# quad_vca_main.net
KiCad netlist of a schematic drawn in EAGLE
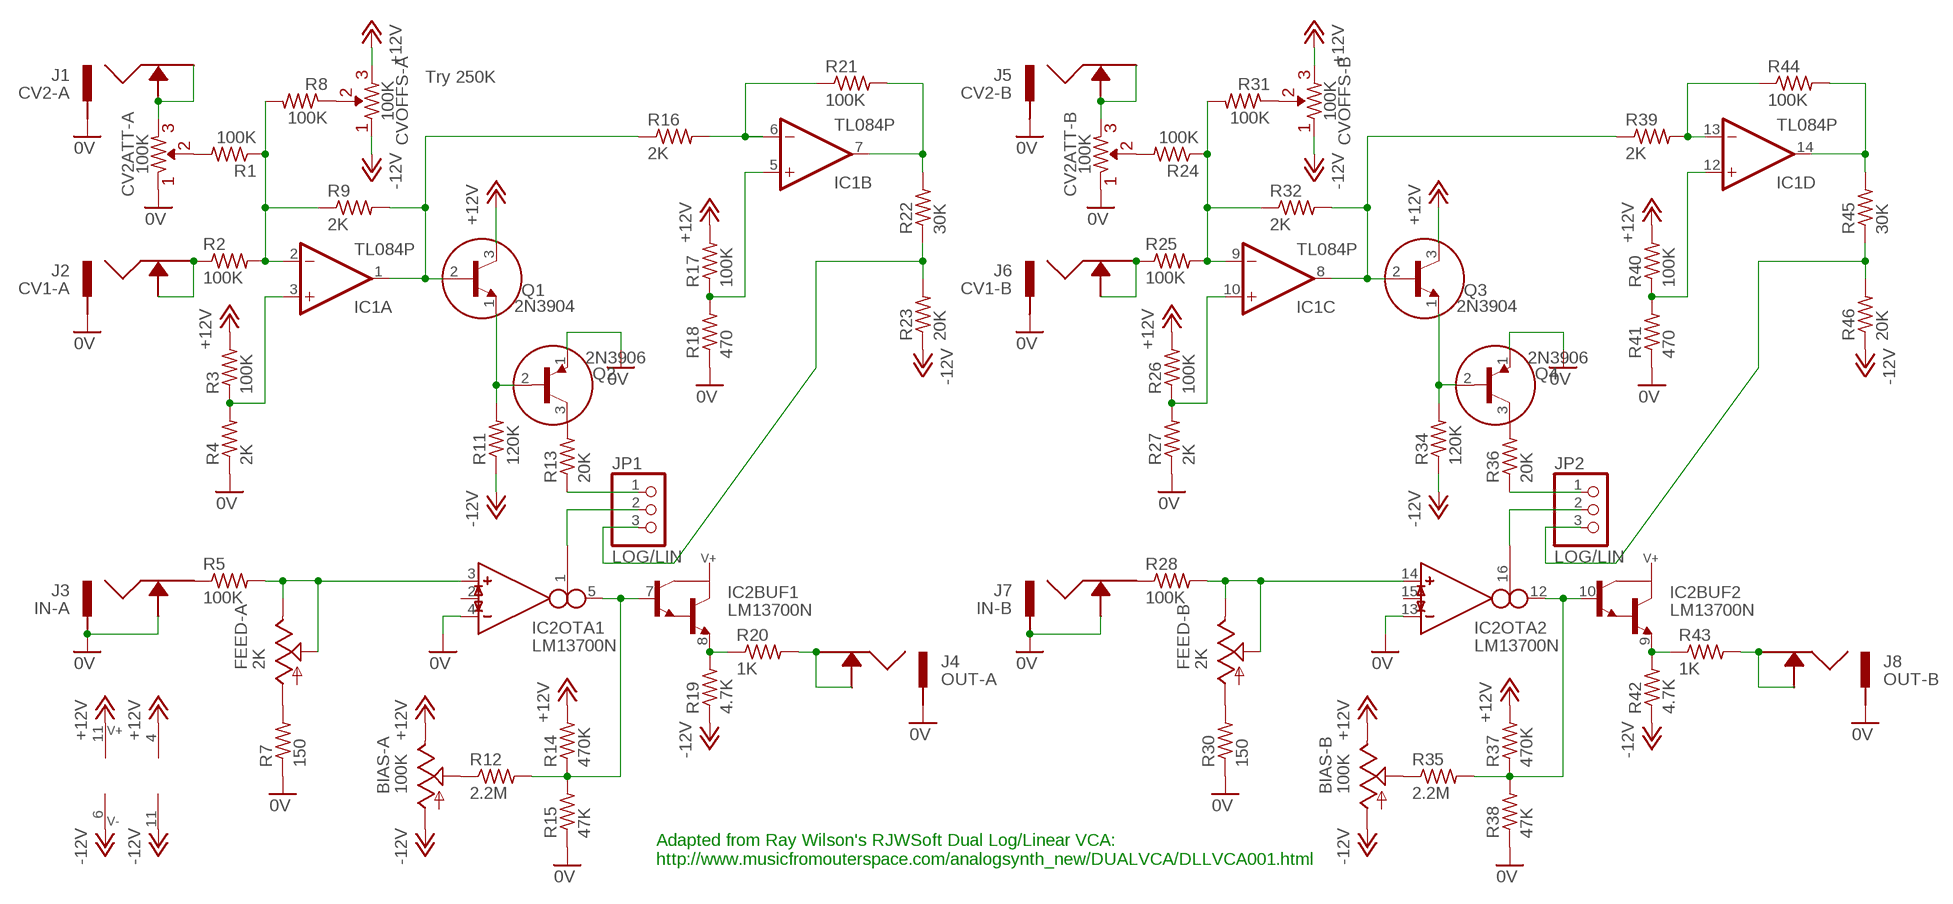
[diagram p0: schematic, sheet 1]

(export (version "E")
  (design (tool "Eeschema 10.0.6"))
  (components
    (comp (ref "BIAS-A")
      (value "100K")
      (footprint "eagle-import:PT-10S")
      (libsource (lib "eagle-import") (part "TRIM_US-PT10S"))
    )
    (comp (ref "BIAS-B")
      (value "100K")
      (footprint "eagle-import:PT-10S")
      (libsource (lib "eagle-import") (part "TRIM_US-PT10S"))
    )
    (comp (ref "CV2ATT-A")
      (value "100K")
      (footprint "eagle-import:R-VAR")
      (libsource (lib "eagle-import") (part "R-VAR"))
    )
    (comp (ref "CV2ATT-B")
      (value "100K")
      (footprint "eagle-import:R-VAR")
      (libsource (lib "eagle-import") (part "R-VAR"))
    )
    (comp (ref "CVOFFS-A")
      (value "100K")
      (footprint "eagle-import:R-VAR")
      (libsource (lib "eagle-import") (part "R-VAR"))
    )
    (comp (ref "CVOFFS-B")
      (value "100K")
      (footprint "eagle-import:R-VAR")
      (libsource (lib "eagle-import") (part "R-VAR"))
    )
    (comp (ref "FEED-A")
      (value "2K")
      (footprint "eagle-import:PT-10S")
      (libsource (lib "eagle-import") (part "TRIM_US-PT10S"))
    )
    (comp (ref "FEED-B")
      (value "2K")
      (footprint "eagle-import:PT-10S")
      (libsource (lib "eagle-import") (part "TRIM_US-PT10S"))
    )
    (comp (ref "IC1")
      (value "TL084P")
      (footprint "eagle-import:DIL14")
      (libsource (lib "eagle-import") (part "TL084P"))
    )
    (comp (ref "IC2")
      (value "LM13700N")
      (footprint "eagle-import:DIL16")
      (libsource (lib "eagle-import") (part "LM13700N"))
    )
    (comp (ref "J1")
      (value "CV2-A")
      (footprint "eagle-import:ACJM-MV35-2S")
      (libsource (lib "eagle-import") (part "ACJM-MV35-2S"))
    )
    (comp (ref "J2")
      (value "CV1-A")
      (footprint "eagle-import:ACJM-MV35-2S")
      (libsource (lib "eagle-import") (part "ACJM-MV35-2S"))
    )
    (comp (ref "J3")
      (value "IN-A")
      (footprint "eagle-import:ACJM-MV35-2S")
      (libsource (lib "eagle-import") (part "ACJM-MV35-2S"))
    )
    (comp (ref "J4")
      (value "OUT-A")
      (footprint "eagle-import:ACJM-MV35-2S")
      (libsource (lib "eagle-import") (part "ACJM-MV35-2S"))
    )
    (comp (ref "J5")
      (value "CV2-B")
      (footprint "eagle-import:ACJM-MV35-2S")
      (libsource (lib "eagle-import") (part "ACJM-MV35-2S"))
    )
    (comp (ref "J6")
      (value "CV1-B")
      (footprint "eagle-import:ACJM-MV35-2S")
      (libsource (lib "eagle-import") (part "ACJM-MV35-2S"))
    )
    (comp (ref "J7")
      (value "IN-B")
      (footprint "eagle-import:ACJM-MV35-2S")
      (libsource (lib "eagle-import") (part "ACJM-MV35-2S"))
    )
    (comp (ref "J8")
      (value "OUT-B")
      (footprint "eagle-import:ACJM-MV35-2S")
      (libsource (lib "eagle-import") (part "ACJM-MV35-2S"))
    )
    (comp (ref "JP1")
      (value "LOG/LIN")
      (footprint "eagle-import:1X03")
      (libsource (lib "eagle-import") (part "PINHD-1X3"))
    )
    (comp (ref "JP2")
      (value "LOG/LIN")
      (footprint "eagle-import:1X03")
      (libsource (lib "eagle-import") (part "PINHD-1X3"))
    )
    (comp (ref "Q1")
      (value "2N3904")
      (footprint "eagle-import:TO92")
      (libsource (lib "eagle-import") (part "2N3904"))
    )
    (comp (ref "Q2")
      (value "2N3906")
      (footprint "eagle-import:TO92")
      (libsource (lib "eagle-import") (part "2N3906"))
    )
    (comp (ref "Q3")
      (value "2N3904")
      (footprint "eagle-import:TO92")
      (libsource (lib "eagle-import") (part "2N3904"))
    )
    (comp (ref "Q4")
      (value "2N3906")
      (footprint "eagle-import:TO92")
      (libsource (lib "eagle-import") (part "2N3906"))
    )
    (comp (ref "R1")
      (value "100K")
      (footprint "eagle-import:0207_7")
      (libsource (lib "eagle-import") (part "R-US_0207/7"))
    )
    (comp (ref "R2")
      (value "100K")
      (footprint "eagle-import:0207_7")
      (libsource (lib "eagle-import") (part "R-US_0207/7"))
    )
    (comp (ref "R3")
      (value "100K")
      (footprint "eagle-import:0207_7")
      (libsource (lib "eagle-import") (part "R-US_0207/7"))
    )
    (comp (ref "R4")
      (value "2K")
      (footprint "eagle-import:0207_7")
      (libsource (lib "eagle-import") (part "R-US_0207/7"))
    )
    (comp (ref "R5")
      (value "100K")
      (footprint "eagle-import:0207_7")
      (libsource (lib "eagle-import") (part "R-US_0207/7"))
    )
    (comp (ref "R7")
      (value "150")
      (footprint "eagle-import:0207_7")
      (libsource (lib "eagle-import") (part "R-US_0207/7"))
    )
    (comp (ref "R8")
      (value "100K")
      (footprint "eagle-import:0207_7")
      (libsource (lib "eagle-import") (part "R-US_0207/7"))
    )
    (comp (ref "R9")
      (value "2K")
      (footprint "eagle-import:0207_7")
      (libsource (lib "eagle-import") (part "R-US_0207/7"))
    )
    (comp (ref "R11")
      (value "120K")
      (footprint "eagle-import:0207_7")
      (libsource (lib "eagle-import") (part "R-US_0207/7"))
    )
    (comp (ref "R12")
      (value "2.2M")
      (footprint "eagle-import:0207_7")
      (libsource (lib "eagle-import") (part "R-US_0207/7"))
    )
    (comp (ref "R13")
      (value "20K")
      (footprint "eagle-import:0207_7")
      (libsource (lib "eagle-import") (part "R-US_0207/7"))
    )
    (comp (ref "R14")
      (value "470K")
      (footprint "eagle-import:0207_7")
      (libsource (lib "eagle-import") (part "R-US_0207/7"))
    )
    (comp (ref "R15")
      (value "47K")
      (footprint "eagle-import:0207_7")
      (libsource (lib "eagle-import") (part "R-US_0207/7"))
    )
    (comp (ref "R16")
      (value "2K")
      (footprint "eagle-import:0207_7")
      (libsource (lib "eagle-import") (part "R-US_0207/7"))
    )
    (comp (ref "R17")
      (value "100K")
      (footprint "eagle-import:0207_7")
      (libsource (lib "eagle-import") (part "R-US_0207/7"))
    )
    (comp (ref "R18")
      (value "470")
      (footprint "eagle-import:0207_7")
      (libsource (lib "eagle-import") (part "R-US_0207/7"))
    )
    (comp (ref "R19")
      (value "4.7K")
      (footprint "eagle-import:0207_7")
      (libsource (lib "eagle-import") (part "R-US_0207/7"))
    )
    (comp (ref "R20")
      (value "1K")
      (footprint "eagle-import:0207_7")
      (libsource (lib "eagle-import") (part "R-US_0207/7"))
    )
    (comp (ref "R21")
      (value "100K")
      (footprint "eagle-import:0207_7")
      (libsource (lib "eagle-import") (part "R-US_0207/7"))
    )
    (comp (ref "R22")
      (value "30K")
      (footprint "eagle-import:0207_7")
      (libsource (lib "eagle-import") (part "R-US_0207/7"))
    )
    (comp (ref "R23")
      (value "20K")
      (footprint "eagle-import:0207_7")
      (libsource (lib "eagle-import") (part "R-US_0207/7"))
    )
    (comp (ref "R24")
      (value "100K")
      (footprint "eagle-import:0207_7")
      (libsource (lib "eagle-import") (part "R-US_0207/7"))
    )
    (comp (ref "R25")
      (value "100K")
      (footprint "eagle-import:0207_7")
      (libsource (lib "eagle-import") (part "R-US_0207/7"))
    )
    (comp (ref "R26")
      (value "100K")
      (footprint "eagle-import:0207_7")
      (libsource (lib "eagle-import") (part "R-US_0207/7"))
    )
    (comp (ref "R27")
      (value "2K")
      (footprint "eagle-import:0207_7")
      (libsource (lib "eagle-import") (part "R-US_0207/7"))
    )
    (comp (ref "R28")
      (value "100K")
      (footprint "eagle-import:0207_7")
      (libsource (lib "eagle-import") (part "R-US_0207/7"))
    )
    (comp (ref "R30")
      (value "150")
      (footprint "eagle-import:0207_7")
      (libsource (lib "eagle-import") (part "R-US_0207/7"))
    )
    (comp (ref "R31")
      (value "100K")
      (footprint "eagle-import:0207_7")
      (libsource (lib "eagle-import") (part "R-US_0207/7"))
    )
    (comp (ref "R32")
      (value "2K")
      (footprint "eagle-import:0207_7")
      (libsource (lib "eagle-import") (part "R-US_0207/7"))
    )
    (comp (ref "R34")
      (value "120K")
      (footprint "eagle-import:0207_7")
      (libsource (lib "eagle-import") (part "R-US_0207/7"))
    )
    (comp (ref "R35")
      (value "2.2M")
      (footprint "eagle-import:0207_7")
      (libsource (lib "eagle-import") (part "R-US_0207/7"))
    )
    (comp (ref "R36")
      (value "20K")
      (footprint "eagle-import:0207_7")
      (libsource (lib "eagle-import") (part "R-US_0207/7"))
    )
    (comp (ref "R37")
      (value "470K")
      (footprint "eagle-import:0207_7")
      (libsource (lib "eagle-import") (part "R-US_0207/7"))
    )
    (comp (ref "R38")
      (value "47K")
      (footprint "eagle-import:0207_7")
      (libsource (lib "eagle-import") (part "R-US_0207/7"))
    )
    (comp (ref "R39")
      (value "2K")
      (footprint "eagle-import:0207_7")
      (libsource (lib "eagle-import") (part "R-US_0207/7"))
    )
    (comp (ref "R40")
      (value "100K")
      (footprint "eagle-import:0207_7")
      (libsource (lib "eagle-import") (part "R-US_0207/7"))
    )
    (comp (ref "R41")
      (value "470")
      (footprint "eagle-import:0207_7")
      (libsource (lib "eagle-import") (part "R-US_0207/7"))
    )
    (comp (ref "R42")
      (value "4.7K")
      (footprint "eagle-import:0207_7")
      (libsource (lib "eagle-import") (part "R-US_0207/7"))
    )
    (comp (ref "R43")
      (value "1K")
      (footprint "eagle-import:0207_7")
      (libsource (lib "eagle-import") (part "R-US_0207/7"))
    )
    (comp (ref "R44")
      (value "100K")
      (footprint "eagle-import:0207_7")
      (libsource (lib "eagle-import") (part "R-US_0207/7"))
    )
    (comp (ref "R45")
      (value "30K")
      (footprint "eagle-import:0207_7")
      (libsource (lib "eagle-import") (part "R-US_0207/7"))
    )
    (comp (ref "R46")
      (value "20K")
      (footprint "eagle-import:0207_7")
      (libsource (lib "eagle-import") (part "R-US_0207/7"))
    )
  )
  (nets
    (net (code "1") (name "+12V") (class "Default")
      (node (ref "BIAS-A") (pin "E") (pinfunction "E_E") (pintype "passive"))
      (node (ref "BIAS-B") (pin "E") (pinfunction "E_E") (pintype "passive"))
      (node (ref "CVOFFS-A") (pin "R2") (pinfunction "2_R2") (pintype "passive"))
      (node (ref "CVOFFS-B") (pin "R2") (pinfunction "2_R2") (pintype "passive"))
      (node (ref "IC1") (pin "4") (pinfunction "V+_4") (pintype "power_in"))
      (node (ref "IC2") (pin "11") (pinfunction "V+_11") (pintype "power_in"))
      (node (ref "Q1") (pin "3") (pinfunction "C_3") (pintype "passive"))
      (node (ref "Q3") (pin "3") (pinfunction "C_3") (pintype "passive"))
      (node (ref "R14") (pin "2") (pinfunction "2_2") (pintype "passive"))
      (node (ref "R17") (pin "2") (pinfunction "2_2") (pintype "passive"))
      (node (ref "R26") (pin "2") (pinfunction "2_2") (pintype "passive"))
      (node (ref "R3") (pin "2") (pinfunction "2_2") (pintype "passive"))
      (node (ref "R37") (pin "2") (pinfunction "2_2") (pintype "passive"))
      (node (ref "R40") (pin "2") (pinfunction "2_2") (pintype "passive"))
    )
    (net (code "2") (name "-12V") (class "Default")
      (node (ref "BIAS-A") (pin "A") (pinfunction "A_A") (pintype "passive"))
      (node (ref "BIAS-B") (pin "A") (pinfunction "A_A") (pintype "passive"))
      (node (ref "CVOFFS-A") (pin "R1") (pinfunction "1_R1") (pintype "passive"))
      (node (ref "CVOFFS-B") (pin "R1") (pinfunction "1_R1") (pintype "passive"))
      (node (ref "IC1") (pin "11") (pinfunction "V-_11") (pintype "power_in"))
      (node (ref "IC2") (pin "6") (pinfunction "V-_6") (pintype "power_in"))
      (node (ref "R11") (pin "1") (pinfunction "1_1") (pintype "passive"))
      (node (ref "R19") (pin "1") (pinfunction "1_1") (pintype "passive"))
      (node (ref "R23") (pin "1") (pinfunction "1_1") (pintype "passive"))
      (node (ref "R34") (pin "1") (pinfunction "1_1") (pintype "passive"))
      (node (ref "R42") (pin "1") (pinfunction "1_1") (pintype "passive"))
      (node (ref "R46") (pin "1") (pinfunction "1_1") (pintype "passive"))
    )
    (net (code "3") (name "0V") (class "Default")
      (node (ref "CV2ATT-A") (pin "R1") (pinfunction "1_R1") (pintype "passive"))
      (node (ref "CV2ATT-B") (pin "R1") (pinfunction "1_R1") (pintype "passive"))
      (node (ref "IC2") (pin "13") (pinfunction "IN_N_13") (pintype "input"))
      (node (ref "IC2") (pin "4") (pinfunction "IN_N_4") (pintype "input"))
      (node (ref "J1") (pin "P$1") (pinfunction "P$1_P$1") (pintype "bidirectional"))
      (node (ref "J2") (pin "P$1") (pinfunction "P$1_P$1") (pintype "bidirectional"))
      (node (ref "J3") (pin "P$1") (pinfunction "P$1_P$1") (pintype "bidirectional"))
      (node (ref "J3") (pin "P$2") (pinfunction "P$3_P$2") (pintype "bidirectional"))
      (node (ref "J4") (pin "P$1") (pinfunction "P$1_P$1") (pintype "bidirectional"))
      (node (ref "J5") (pin "P$1") (pinfunction "P$1_P$1") (pintype "bidirectional"))
      (node (ref "J6") (pin "P$1") (pinfunction "P$1_P$1") (pintype "bidirectional"))
      (node (ref "J7") (pin "P$1") (pinfunction "P$1_P$1") (pintype "bidirectional"))
      (node (ref "J7") (pin "P$2") (pinfunction "P$3_P$2") (pintype "bidirectional"))
      (node (ref "J8") (pin "P$1") (pinfunction "P$1_P$1") (pintype "bidirectional"))
      (node (ref "Q2") (pin "1") (pinfunction "E_1") (pintype "passive"))
      (node (ref "Q4") (pin "1") (pinfunction "E_1") (pintype "passive"))
      (node (ref "R15") (pin "1") (pinfunction "1_1") (pintype "passive"))
      (node (ref "R18") (pin "1") (pinfunction "1_1") (pintype "passive"))
      (node (ref "R27") (pin "1") (pinfunction "1_1") (pintype "passive"))
      (node (ref "R30") (pin "1") (pinfunction "1_1") (pintype "passive"))
      (node (ref "R38") (pin "1") (pinfunction "1_1") (pintype "passive"))
      (node (ref "R4") (pin "1") (pinfunction "1_1") (pintype "passive"))
      (node (ref "R41") (pin "1") (pinfunction "1_1") (pintype "passive"))
      (node (ref "R7") (pin "1") (pinfunction "1_1") (pintype "passive"))
    )
    (net (code "4") (name "Net-(BIAS-A-PadS)") (class "Default")
      (node (ref "BIAS-A") (pin "S") (pinfunction "S_S") (pintype "passive"))
      (node (ref "R12") (pin "1") (pinfunction "1_1") (pintype "passive"))
    )
    (net (code "5") (name "Net-(BIAS-B-PadS)") (class "Default")
      (node (ref "BIAS-B") (pin "S") (pinfunction "S_S") (pintype "passive"))
      (node (ref "R35") (pin "1") (pinfunction "1_1") (pintype "passive"))
    )
    (net (code "6") (name "Net-(CV2ATT-A-2)") (class "Default")
      (node (ref "CV2ATT-A") (pin "R2") (pinfunction "2_R2") (pintype "passive"))
      (node (ref "J1") (pin "P$2") (pinfunction "P$3_P$2") (pintype "bidirectional"))
      (node (ref "J1") (pin "P$3") (pinfunction "P$2_P$3") (pintype "bidirectional"))
    )
    (net (code "7") (name "Net-(CV2ATT-A-P$1)") (class "Default")
      (node (ref "CV2ATT-A") (pin "VAR") (pinfunction "P$1_VAR") (pintype "passive"))
      (node (ref "R1") (pin "2") (pinfunction "2_2") (pintype "passive"))
    )
    (net (code "8") (name "Net-(CV2ATT-B-2)") (class "Default")
      (node (ref "CV2ATT-B") (pin "R2") (pinfunction "2_R2") (pintype "passive"))
      (node (ref "J5") (pin "P$2") (pinfunction "P$3_P$2") (pintype "bidirectional"))
      (node (ref "J5") (pin "P$3") (pinfunction "P$2_P$3") (pintype "bidirectional"))
    )
    (net (code "9") (name "Net-(CV2ATT-B-P$1)") (class "Default")
      (node (ref "CV2ATT-B") (pin "VAR") (pinfunction "P$1_VAR") (pintype "passive"))
      (node (ref "R24") (pin "2") (pinfunction "2_2") (pintype "passive"))
    )
    (net (code "10") (name "Net-(CVOFFS-A-P$1)") (class "Default")
      (node (ref "CVOFFS-A") (pin "VAR") (pinfunction "P$1_VAR") (pintype "passive"))
      (node (ref "R8") (pin "1") (pinfunction "1_1") (pintype "passive"))
    )
    (net (code "11") (name "Net-(CVOFFS-B-P$1)") (class "Default")
      (node (ref "CVOFFS-B") (pin "VAR") (pinfunction "P$1_VAR") (pintype "passive"))
      (node (ref "R31") (pin "1") (pinfunction "1_1") (pintype "passive"))
    )
    (net (code "12") (name "Net-(FEED-A-PadA)") (class "Default")
      (node (ref "FEED-A") (pin "A") (pinfunction "A_A") (pintype "passive"))
      (node (ref "R7") (pin "2") (pinfunction "2_2") (pintype "passive"))
    )
    (net (code "13") (name "Net-(FEED-B-PadA)") (class "Default")
      (node (ref "FEED-B") (pin "A") (pinfunction "A_A") (pintype "passive"))
      (node (ref "R30") (pin "2") (pinfunction "2_2") (pintype "passive"))
    )
    (net (code "14") (name "Net-(IC1A-+IN)") (class "Default")
      (node (ref "IC1") (pin "3") (pinfunction "+IN_3") (pintype "input"))
      (node (ref "R3") (pin "1") (pinfunction "1_1") (pintype "passive"))
      (node (ref "R4") (pin "2") (pinfunction "2_2") (pintype "passive"))
    )
    (net (code "15") (name "Net-(IC1A--IN)") (class "Default")
      (node (ref "IC1") (pin "2") (pinfunction "-IN_2") (pintype "input"))
      (node (ref "R1") (pin "1") (pinfunction "1_1") (pintype "passive"))
      (node (ref "R2") (pin "2") (pinfunction "2_2") (pintype "passive"))
      (node (ref "R8") (pin "2") (pinfunction "2_2") (pintype "passive"))
      (node (ref "R9") (pin "1") (pinfunction "1_1") (pintype "passive"))
    )
    (net (code "16") (name "Net-(IC1A-OUT)") (class "Default")
      (node (ref "IC1") (pin "1") (pinfunction "OUT_1") (pintype "output"))
      (node (ref "Q1") (pin "2") (pinfunction "B_2") (pintype "passive"))
      (node (ref "R16") (pin "1") (pinfunction "1_1") (pintype "passive"))
      (node (ref "R9") (pin "2") (pinfunction "2_2") (pintype "passive"))
    )
    (net (code "17") (name "Net-(IC1B-+IN)") (class "Default")
      (node (ref "IC1") (pin "5") (pinfunction "+IN_5") (pintype "input"))
      (node (ref "R17") (pin "1") (pinfunction "1_1") (pintype "passive"))
      (node (ref "R18") (pin "2") (pinfunction "2_2") (pintype "passive"))
    )
    (net (code "18") (name "Net-(IC1B--IN)") (class "Default")
      (node (ref "IC1") (pin "6") (pinfunction "-IN_6") (pintype "input"))
      (node (ref "R16") (pin "2") (pinfunction "2_2") (pintype "passive"))
      (node (ref "R21") (pin "1") (pinfunction "1_1") (pintype "passive"))
    )
    (net (code "19") (name "Net-(IC1B-OUT)") (class "Default")
      (node (ref "IC1") (pin "7") (pinfunction "OUT_7") (pintype "output"))
      (node (ref "R21") (pin "2") (pinfunction "2_2") (pintype "passive"))
      (node (ref "R22") (pin "2") (pinfunction "2_2") (pintype "passive"))
    )
    (net (code "20") (name "Net-(IC1C-+IN)") (class "Default")
      (node (ref "IC1") (pin "10") (pinfunction "+IN_10") (pintype "input"))
      (node (ref "R26") (pin "1") (pinfunction "1_1") (pintype "passive"))
      (node (ref "R27") (pin "2") (pinfunction "2_2") (pintype "passive"))
    )
    (net (code "21") (name "Net-(IC1C--IN)") (class "Default")
      (node (ref "IC1") (pin "9") (pinfunction "-IN_9") (pintype "input"))
      (node (ref "R24") (pin "1") (pinfunction "1_1") (pintype "passive"))
      (node (ref "R25") (pin "2") (pinfunction "2_2") (pintype "passive"))
      (node (ref "R31") (pin "2") (pinfunction "2_2") (pintype "passive"))
      (node (ref "R32") (pin "1") (pinfunction "1_1") (pintype "passive"))
    )
    (net (code "22") (name "Net-(IC1C-OUT)") (class "Default")
      (node (ref "IC1") (pin "8") (pinfunction "OUT_8") (pintype "output"))
      (node (ref "Q3") (pin "2") (pinfunction "B_2") (pintype "passive"))
      (node (ref "R32") (pin "2") (pinfunction "2_2") (pintype "passive"))
      (node (ref "R39") (pin "1") (pinfunction "1_1") (pintype "passive"))
    )
    (net (code "23") (name "Net-(IC1D-+IN)") (class "Default")
      (node (ref "IC1") (pin "12") (pinfunction "+IN_12") (pintype "input"))
      (node (ref "R40") (pin "1") (pinfunction "1_1") (pintype "passive"))
      (node (ref "R41") (pin "2") (pinfunction "2_2") (pintype "passive"))
    )
    (net (code "24") (name "Net-(IC1D--IN)") (class "Default")
      (node (ref "IC1") (pin "13") (pinfunction "-IN_13") (pintype "input"))
      (node (ref "R39") (pin "2") (pinfunction "2_2") (pintype "passive"))
      (node (ref "R44") (pin "1") (pinfunction "1_1") (pintype "passive"))
    )
    (net (code "25") (name "Net-(IC1D-OUT)") (class "Default")
      (node (ref "IC1") (pin "14") (pinfunction "OUT_14") (pintype "output"))
      (node (ref "R44") (pin "2") (pinfunction "2_2") (pintype "passive"))
      (node (ref "R45") (pin "2") (pinfunction "2_2") (pintype "passive"))
    )
    (net (code "26") (name "Net-(IC2A-B)") (class "Default")
      (node (ref "IC2") (pin "5") (pinfunction "OUT_5") (pintype "output"))
      (node (ref "IC2") (pin "7") (pinfunction "B_7") (pintype "passive"))
      (node (ref "R12") (pin "2") (pinfunction "2_2") (pintype "passive"))
      (node (ref "R14") (pin "1") (pinfunction "1_1") (pintype "passive"))
      (node (ref "R15") (pin "2") (pinfunction "2_2") (pintype "passive"))
    )
    (net (code "27") (name "Net-(IC2A-E)") (class "Default")
      (node (ref "IC2") (pin "8") (pinfunction "E_8") (pintype "passive"))
      (node (ref "R19") (pin "2") (pinfunction "2_2") (pintype "passive"))
      (node (ref "R20") (pin "1") (pinfunction "1_1") (pintype "passive"))
    )
    (net (code "28") (name "Net-(IC2B-B)") (class "Default")
      (node (ref "IC2") (pin "10") (pinfunction "B_10") (pintype "passive"))
      (node (ref "IC2") (pin "12") (pinfunction "OUT_12") (pintype "output"))
      (node (ref "R35") (pin "2") (pinfunction "2_2") (pintype "passive"))
      (node (ref "R37") (pin "1") (pinfunction "1_1") (pintype "passive"))
      (node (ref "R38") (pin "2") (pinfunction "2_2") (pintype "passive"))
    )
    (net (code "29") (name "Net-(IC2B-E)") (class "Default")
      (node (ref "IC2") (pin "9") (pinfunction "E_9") (pintype "passive"))
      (node (ref "R42") (pin "2") (pinfunction "2_2") (pintype "passive"))
      (node (ref "R43") (pin "1") (pinfunction "1_1") (pintype "passive"))
    )
    (net (code "30") (name "Net-(IC2C-IN_P)") (class "Default")
      (node (ref "FEED-A") (pin "E") (pinfunction "E_E") (pintype "passive"))
      (node (ref "FEED-A") (pin "S") (pinfunction "S_S") (pintype "passive"))
      (node (ref "IC2") (pin "3") (pinfunction "IN_P_3") (pintype "input"))
      (node (ref "R5") (pin "2") (pinfunction "2_2") (pintype "passive"))
    )
    (net (code "31") (name "Net-(IC2C-I_BIAS)") (class "Default")
      (node (ref "IC2") (pin "1") (pinfunction "I_BIAS_1") (pintype "input"))
      (node (ref "JP1") (pin "2") (pinfunction "2_2") (pintype "passive"))
    )
    (net (code "32") (name "Net-(IC2D-IN_P)") (class "Default")
      (node (ref "FEED-B") (pin "E") (pinfunction "E_E") (pintype "passive"))
      (node (ref "FEED-B") (pin "S") (pinfunction "S_S") (pintype "passive"))
      (node (ref "IC2") (pin "14") (pinfunction "IN_P_14") (pintype "input"))
      (node (ref "R28") (pin "2") (pinfunction "2_2") (pintype "passive"))
    )
    (net (code "33") (name "Net-(IC2D-I_BIAS)") (class "Default")
      (node (ref "IC2") (pin "16") (pinfunction "I_BIAS_16") (pintype "input"))
      (node (ref "JP2") (pin "2") (pinfunction "2_2") (pintype "passive"))
    )
    (net (code "34") (name "Net-(J2-P$2)") (class "Default")
      (node (ref "J2") (pin "P$2") (pinfunction "P$3_P$2") (pintype "bidirectional"))
      (node (ref "J2") (pin "P$3") (pinfunction "P$2_P$3") (pintype "bidirectional"))
      (node (ref "R2") (pin "1") (pinfunction "1_1") (pintype "passive"))
    )
    (net (code "35") (name "Net-(J3-P$2)") (class "Default")
      (node (ref "J3") (pin "P$3") (pinfunction "P$2_P$3") (pintype "bidirectional"))
      (node (ref "R5") (pin "1") (pinfunction "1_1") (pintype "passive"))
    )
    (net (code "36") (name "Net-(J4-P$2)") (class "Default")
      (node (ref "J4") (pin "P$2") (pinfunction "P$3_P$2") (pintype "bidirectional"))
      (node (ref "J4") (pin "P$3") (pinfunction "P$2_P$3") (pintype "bidirectional"))
      (node (ref "R20") (pin "2") (pinfunction "2_2") (pintype "passive"))
    )
    (net (code "37") (name "Net-(J6-P$2)") (class "Default")
      (node (ref "J6") (pin "P$2") (pinfunction "P$3_P$2") (pintype "bidirectional"))
      (node (ref "J6") (pin "P$3") (pinfunction "P$2_P$3") (pintype "bidirectional"))
      (node (ref "R25") (pin "1") (pinfunction "1_1") (pintype "passive"))
    )
    (net (code "38") (name "Net-(J7-P$2)") (class "Default")
      (node (ref "J7") (pin "P$3") (pinfunction "P$2_P$3") (pintype "bidirectional"))
      (node (ref "R28") (pin "1") (pinfunction "1_1") (pintype "passive"))
    )
    (net (code "39") (name "Net-(J8-P$2)") (class "Default")
      (node (ref "J8") (pin "P$2") (pinfunction "P$3_P$2") (pintype "bidirectional"))
      (node (ref "J8") (pin "P$3") (pinfunction "P$2_P$3") (pintype "bidirectional"))
      (node (ref "R43") (pin "2") (pinfunction "2_2") (pintype "passive"))
    )
    (net (code "40") (name "Net-(JP1-Pad1)") (class "Default")
      (node (ref "JP1") (pin "1") (pinfunction "1_1") (pintype "passive"))
      (node (ref "R13") (pin "1") (pinfunction "1_1") (pintype "passive"))
    )
    (net (code "41") (name "Net-(JP1-Pad3)") (class "Default")
      (node (ref "JP1") (pin "3") (pinfunction "3_3") (pintype "passive"))
      (node (ref "R22") (pin "1") (pinfunction "1_1") (pintype "passive"))
      (node (ref "R23") (pin "2") (pinfunction "2_2") (pintype "passive"))
    )
    (net (code "42") (name "Net-(JP2-Pad1)") (class "Default")
      (node (ref "JP2") (pin "1") (pinfunction "1_1") (pintype "passive"))
      (node (ref "R36") (pin "1") (pinfunction "1_1") (pintype "passive"))
    )
    (net (code "43") (name "Net-(JP2-Pad3)") (class "Default")
      (node (ref "JP2") (pin "3") (pinfunction "3_3") (pintype "passive"))
      (node (ref "R45") (pin "1") (pinfunction "1_1") (pintype "passive"))
      (node (ref "R46") (pin "2") (pinfunction "2_2") (pintype "passive"))
    )
    (net (code "44") (name "Net-(Q1-E)") (class "Default")
      (node (ref "Q1") (pin "1") (pinfunction "E_1") (pintype "passive"))
      (node (ref "Q2") (pin "2") (pinfunction "B_2") (pintype "passive"))
      (node (ref "R11") (pin "2") (pinfunction "2_2") (pintype "passive"))
    )
    (net (code "45") (name "Net-(Q2-C)") (class "Default")
      (node (ref "Q2") (pin "3") (pinfunction "C_3") (pintype "passive"))
      (node (ref "R13") (pin "2") (pinfunction "2_2") (pintype "passive"))
    )
    (net (code "46") (name "Net-(Q3-E)") (class "Default")
      (node (ref "Q3") (pin "1") (pinfunction "E_1") (pintype "passive"))
      (node (ref "Q4") (pin "2") (pinfunction "B_2") (pintype "passive"))
      (node (ref "R34") (pin "2") (pinfunction "2_2") (pintype "passive"))
    )
    (net (code "47") (name "Net-(Q4-C)") (class "Default")
      (node (ref "Q4") (pin "3") (pinfunction "C_3") (pintype "passive"))
      (node (ref "R36") (pin "2") (pinfunction "2_2") (pintype "passive"))
    )
    (net (code "48") (name "unconnected-(IC2C-I_DIODE-Pad2)") (class "Default")
      (node (ref "IC2") (pin "2") (pinfunction "I_DIODE_2") (pintype "input"))
    )
    (net (code "49") (name "unconnected-(IC2D-I_DIODE-Pad15)") (class "Default")
      (node (ref "IC2") (pin "15") (pinfunction "I_DIODE_15") (pintype "input"))
    )
  )
)
